# Zavrsni.net
KiCad netlist of a schematic drawn in Altium Designer
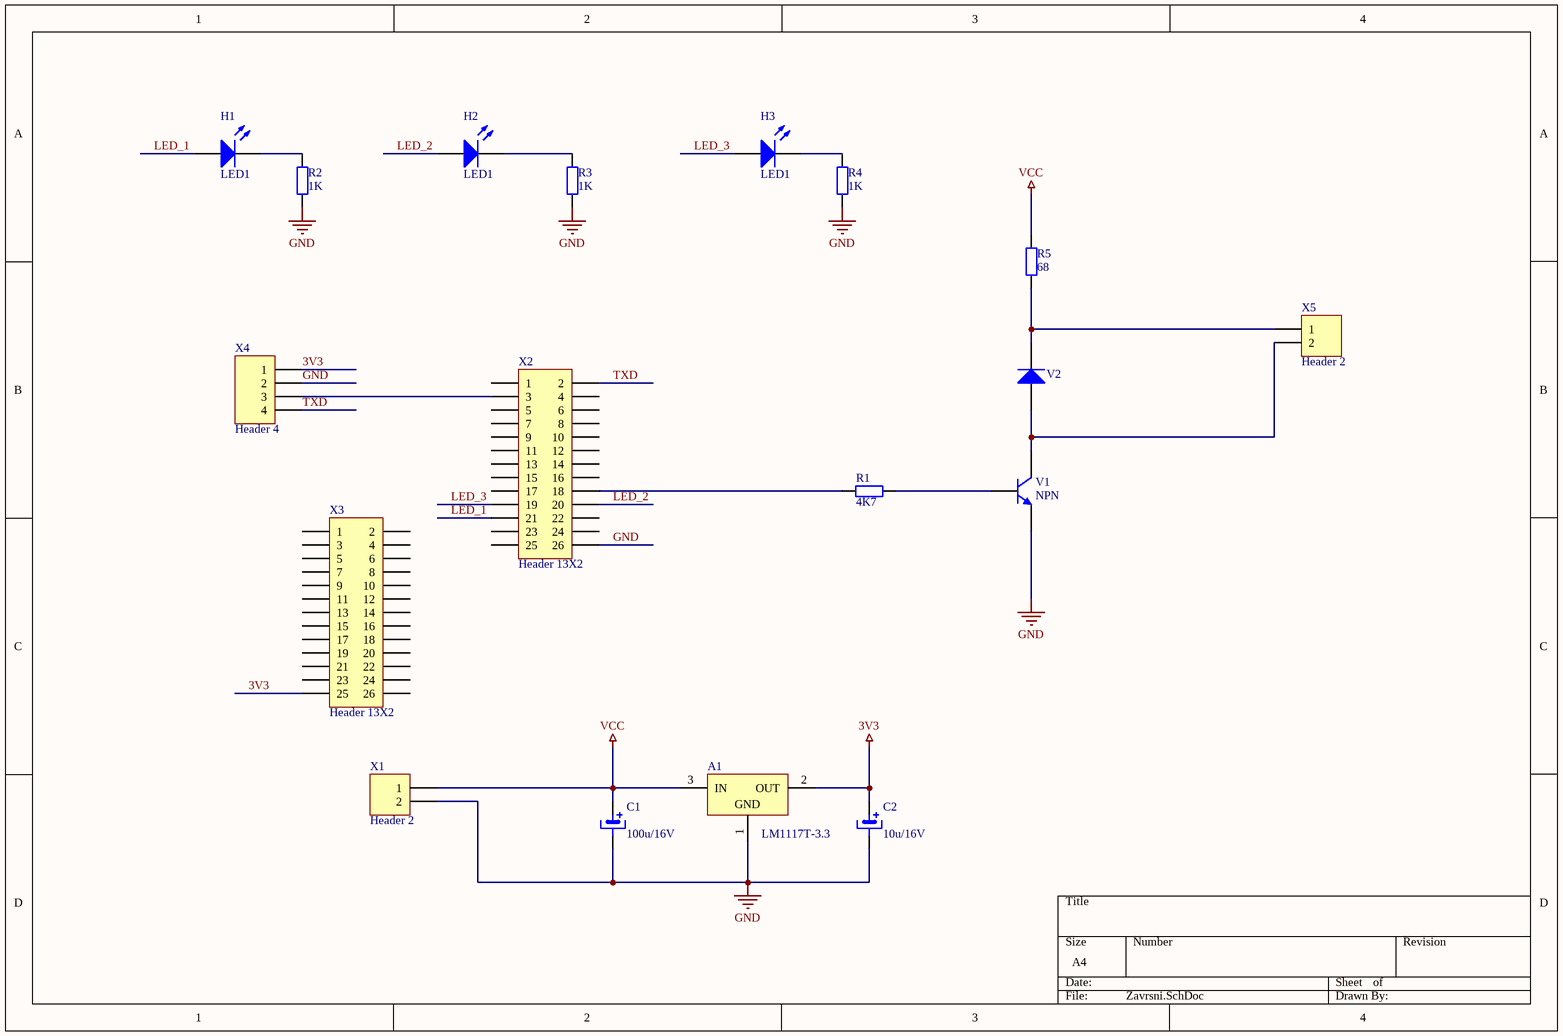
[diagram p0: Zavrsni.SchDoc]

(export (version "E")
  (design (tool "Eeschema 10.0.6"))
  (components
    (comp (ref "A1")
      (value "LM1117T-3.3")
      (footprint "T03B")
      (description "800mA Low-Dropout Linear Regulator, 3-pin TO-220")
      (fields
        (field (name "MANUFACTURER") "National Semiconductor")
        (field (name "PUBLISHER") "Altium Limited")
      )
      (libsource (lib "NSC LDO") (part "LM1117T-3.3"))
    )
    (comp (ref "C1")
      (value "100u/16V")
      (footprint "CAPPR2-5x6.8")
      (description "Electrolytic capacitor")
      (libsource (lib "Zavrsni") (part "Elko"))
    )
    (comp (ref "C2")
      (value "10u/16V")
      (footprint "CAPPR2-5x6.8")
      (description "Electrolytic capacitor")
      (libsource (lib "Zavrsni") (part "Elko"))
    )
    (comp (ref "H1")
      (value "LED1")
      (footprint "LED dioda")
      (description "LED zelena")
      (fields (field (name "PUBLISHER") "Altium Limited"))
      (libsource (lib "Miscellaneous Devices") (part "LED1"))
    )
    (comp (ref "H2")
      (value "LED1")
      (footprint "LED dioda")
      (description "LED žuta")
      (fields (field (name "PUBLISHER") "Altium Limited"))
      (libsource (lib "Miscellaneous Devices") (part "LED1"))
    )
    (comp (ref "H3")
      (value "LED1")
      (footprint "LED dioda")
      (description "LED crvena")
      (fields (field (name "PUBLISHER") "Altium Limited"))
      (libsource (lib "Miscellaneous Devices") (part "LED1"))
    )
    (comp (ref "R1")
      (value "4K7")
      (footprint "AXIAL-0.4")
      (description "Resistor")
      (fields (field (name "PUBLISHER") "Altium Limited"))
      (libsource (lib "") (part "Res2_1"))
    )
    (comp (ref "R2")
      (value "1K")
      (footprint "AXIAL-0.4")
      (description "Resistor")
      (fields (field (name "PUBLISHER") "Altium Limited"))
      (libsource (lib "Miscellaneous Devices") (part "Res2"))
    )
    (comp (ref "R3")
      (value "1K")
      (footprint "AXIAL-0.4")
      (description "Resistor")
      (fields (field (name "PUBLISHER") "Altium Limited"))
      (libsource (lib "Miscellaneous Devices") (part "Res2"))
    )
    (comp (ref "R4")
      (value "1K")
      (footprint "AXIAL-0.4")
      (description "Resistor")
      (fields (field (name "PUBLISHER") "Altium Limited"))
      (libsource (lib "Miscellaneous Devices") (part "Res2"))
    )
    (comp (ref "R5")
      (value "68")
      (footprint "AXIAL-0.4")
      (description "Resistor")
      (fields (field (name "PUBLISHER") "Altium Limited"))
      (libsource (lib "Miscellaneous Devices") (part "Res2"))
    )
    (comp (ref "V1")
      (value "NPN")
      (footprint "TO-226-AA")
      (description "NPN Bipolar Transistor")
      (fields (field (name "PUBLISHER") "Altium Limited"))
      (libsource (lib "Miscellaneous Devices") (part "NPN"))
    )
    (comp (ref "V2")
      (value "Diode 1N4004")
      (footprint "DO-41")
      (description "1 Amp General Purpose Rectifier")
      (fields (field (name "PUBLISHER") "Altium Limited"))
      (libsource (lib "Miscellaneous Devices") (part "Diode 1N4004"))
    )
    (comp (ref "X1")
      (value "Header 2")
      (footprint "HDR1X2")
      (description "Header, 2-Pin")
      (fields (field (name "PUBLISHER") "Altium Limited"))
      (libsource (lib "") (part "Header 2_1"))
    )
    (comp (ref "X2")
      (value "Header 13X2")
      (footprint "HDR2X13")
      (description "Header, 13-Pin, Dual row")
      (fields (field (name "PUBLISHER") "Altium Limited"))
      (libsource (lib "Miscellaneous Connectors") (part "Header 13X2"))
    )
    (comp (ref "X3")
      (value "Header 13X2")
      (footprint "HDR2X13")
      (description "Header, 13-Pin, Dual row")
      (fields (field (name "PUBLISHER") "Altium Limited"))
      (libsource (lib "Miscellaneous Connectors") (part "Header 13X2"))
    )
    (comp (ref "X4")
      (value "Header 4")
      (footprint "HDR1X4")
      (description "Header, 4-Pin")
      (fields (field (name "PUBLISHER") "Altium Limited"))
      (libsource (lib "Miscellaneous Connectors") (part "Header 4"))
    )
    (comp (ref "X5")
      (value "Header 2")
      (footprint "HDR1X2")
      (description "Header, 2-Pin")
      (fields (field (name "PUBLISHER") "Altium Limited"))
      (libsource (lib "Miscellaneous Connectors") (part "Header 2"))
    )
  )
  (nets
    (net (code "1") (name "/LED_1") (class "Default")
      (node (ref "H1") (pin "1") (pinfunction "A_1") (pintype "passive"))
      (node (ref "X2") (pin "21") (pinfunction "21_21") (pintype "passive"))
    )
    (net (code "2") (name "/LED_2") (class "Default")
      (node (ref "H2") (pin "1") (pinfunction "A_1") (pintype "passive"))
      (node (ref "X2") (pin "20") (pinfunction "20_20") (pintype "passive"))
    )
    (net (code "3") (name "/LED_3") (class "Default")
      (node (ref "H3") (pin "1") (pinfunction "A_1") (pintype "passive"))
      (node (ref "X2") (pin "19") (pinfunction "19_19") (pintype "passive"))
    )
    (net (code "4") (name "/TXD") (class "Default")
      (node (ref "X2") (pin "2") (pinfunction "2_2") (pintype "passive"))
      (node (ref "X4") (pin "4") (pinfunction "4_4") (pintype "passive"))
    )
    (net (code "5") (name "3V3") (class "Default")
      (node (ref "A1") (pin "2") (pinfunction "OUT_2") (pintype "power_in"))
      (node (ref "C2") (pin "1") (pinfunction "1_1") (pintype "passive"))
      (node (ref "X3") (pin "25") (pinfunction "25_25") (pintype "passive"))
      (node (ref "X4") (pin "1") (pinfunction "1_1") (pintype "passive"))
    )
    (net (code "6") (name "GND") (class "Default")
      (node (ref "A1") (pin "1") (pinfunction "GND_1") (pintype "power_in"))
      (node (ref "C1") (pin "2") (pinfunction "2_2") (pintype "passive"))
      (node (ref "C2") (pin "2") (pinfunction "2_2") (pintype "passive"))
      (node (ref "R2") (pin "1") (pinfunction "1_1") (pintype "passive"))
      (node (ref "R3") (pin "1") (pinfunction "1_1") (pintype "passive"))
      (node (ref "R4") (pin "1") (pinfunction "1_1") (pintype "passive"))
      (node (ref "V1") (pin "3") (pinfunction "E_3") (pintype "passive"))
      (node (ref "X1") (pin "2") (pinfunction "2_2") (pintype "passive"))
      (node (ref "X2") (pin "26") (pinfunction "26_26") (pintype "passive"))
      (node (ref "X4") (pin "2") (pinfunction "2_2") (pintype "passive"))
    )
    (net (code "7") (name "Net-(H1-K)") (class "Default")
      (node (ref "H1") (pin "2") (pinfunction "K_2") (pintype "passive"))
      (node (ref "R2") (pin "2") (pinfunction "2_2") (pintype "passive"))
    )
    (net (code "8") (name "Net-(H2-K)") (class "Default")
      (node (ref "H2") (pin "2") (pinfunction "K_2") (pintype "passive"))
      (node (ref "R3") (pin "2") (pinfunction "2_2") (pintype "passive"))
    )
    (net (code "9") (name "Net-(H3-K)") (class "Default")
      (node (ref "H3") (pin "2") (pinfunction "K_2") (pintype "passive"))
      (node (ref "R4") (pin "2") (pinfunction "2_2") (pintype "passive"))
    )
    (net (code "10") (name "Net-(R1-Pad1)") (class "Default")
      (node (ref "R1") (pin "1") (pinfunction "1_1") (pintype "passive"))
      (node (ref "X2") (pin "18") (pinfunction "18_18") (pintype "passive"))
    )
    (net (code "11") (name "Net-(V1-B)") (class "Default")
      (node (ref "R1") (pin "2") (pinfunction "2_2") (pintype "passive"))
      (node (ref "V1") (pin "2") (pinfunction "B_2") (pintype "passive"))
    )
    (net (code "12") (name "Net-(V1-C)") (class "Default")
      (node (ref "V1") (pin "1") (pinfunction "C_1") (pintype "passive"))
      (node (ref "V2") (pin "1") (pinfunction "A_1") (pintype "passive"))
      (node (ref "X5") (pin "2") (pinfunction "2_2") (pintype "passive"))
    )
    (net (code "13") (name "Net-(V2-K)") (class "Default")
      (node (ref "R5") (pin "1") (pinfunction "1_1") (pintype "passive"))
      (node (ref "V2") (pin "2") (pinfunction "K_2") (pintype "passive"))
      (node (ref "X5") (pin "1") (pinfunction "1_1") (pintype "passive"))
    )
    (net (code "14") (name "Net-(X2-Pad3)") (class "Default")
      (node (ref "X2") (pin "3") (pinfunction "3_3") (pintype "passive"))
      (node (ref "X4") (pin "3") (pinfunction "3_3") (pintype "passive"))
    )
    (net (code "15") (name "VCC") (class "Default")
      (node (ref "A1") (pin "3") (pinfunction "IN_3") (pintype "power_in"))
      (node (ref "C1") (pin "1") (pinfunction "1_1") (pintype "passive"))
      (node (ref "R5") (pin "2") (pinfunction "2_2") (pintype "passive"))
      (node (ref "X1") (pin "1") (pinfunction "1_1") (pintype "passive"))
    )
    (net (code "16") (name "unconnected-(X2-Pad1)") (class "Default")
      (node (ref "X2") (pin "1") (pinfunction "1_1") (pintype "passive"))
    )
    (net (code "17") (name "unconnected-(X2-Pad4)") (class "Default")
      (node (ref "X2") (pin "4") (pinfunction "4_4") (pintype "passive"))
    )
    (net (code "18") (name "unconnected-(X2-Pad5)") (class "Default")
      (node (ref "X2") (pin "5") (pinfunction "5_5") (pintype "passive"))
    )
    (net (code "19") (name "unconnected-(X2-Pad6)") (class "Default")
      (node (ref "X2") (pin "6") (pinfunction "6_6") (pintype "passive"))
    )
    (net (code "20") (name "unconnected-(X2-Pad7)") (class "Default")
      (node (ref "X2") (pin "7") (pinfunction "7_7") (pintype "passive"))
    )
    (net (code "21") (name "unconnected-(X2-Pad8)") (class "Default")
      (node (ref "X2") (pin "8") (pinfunction "8_8") (pintype "passive"))
    )
    (net (code "22") (name "unconnected-(X2-Pad9)") (class "Default")
      (node (ref "X2") (pin "9") (pinfunction "9_9") (pintype "passive"))
    )
    (net (code "23") (name "unconnected-(X2-Pad10)") (class "Default")
      (node (ref "X2") (pin "10") (pinfunction "10_10") (pintype "passive"))
    )
    (net (code "24") (name "unconnected-(X2-Pad11)") (class "Default")
      (node (ref "X2") (pin "11") (pinfunction "11_11") (pintype "passive"))
    )
    (net (code "25") (name "unconnected-(X2-Pad12)") (class "Default")
      (node (ref "X2") (pin "12") (pinfunction "12_12") (pintype "passive"))
    )
    (net (code "26") (name "unconnected-(X2-Pad13)") (class "Default")
      (node (ref "X2") (pin "13") (pinfunction "13_13") (pintype "passive"))
    )
    (net (code "27") (name "unconnected-(X2-Pad14)") (class "Default")
      (node (ref "X2") (pin "14") (pinfunction "14_14") (pintype "passive"))
    )
    (net (code "28") (name "unconnected-(X2-Pad15)") (class "Default")
      (node (ref "X2") (pin "15") (pinfunction "15_15") (pintype "passive"))
    )
    (net (code "29") (name "unconnected-(X2-Pad16)") (class "Default")
      (node (ref "X2") (pin "16") (pinfunction "16_16") (pintype "passive"))
    )
    (net (code "30") (name "unconnected-(X2-Pad17)") (class "Default")
      (node (ref "X2") (pin "17") (pinfunction "17_17") (pintype "passive"))
    )
    (net (code "31") (name "unconnected-(X2-Pad22)") (class "Default")
      (node (ref "X2") (pin "22") (pinfunction "22_22") (pintype "passive"))
    )
    (net (code "32") (name "unconnected-(X2-Pad23)") (class "Default")
      (node (ref "X2") (pin "23") (pinfunction "23_23") (pintype "passive"))
    )
    (net (code "33") (name "unconnected-(X2-Pad24)") (class "Default")
      (node (ref "X2") (pin "24") (pinfunction "24_24") (pintype "passive"))
    )
    (net (code "34") (name "unconnected-(X2-Pad25)") (class "Default")
      (node (ref "X2") (pin "25") (pinfunction "25_25") (pintype "passive"))
    )
    (net (code "35") (name "unconnected-(X3-Pad1)") (class "Default")
      (node (ref "X3") (pin "1") (pinfunction "1_1") (pintype "passive"))
    )
    (net (code "36") (name "unconnected-(X3-Pad2)") (class "Default")
      (node (ref "X3") (pin "2") (pinfunction "2_2") (pintype "passive"))
    )
    (net (code "37") (name "unconnected-(X3-Pad3)") (class "Default")
      (node (ref "X3") (pin "3") (pinfunction "3_3") (pintype "passive"))
    )
    (net (code "38") (name "unconnected-(X3-Pad4)") (class "Default")
      (node (ref "X3") (pin "4") (pinfunction "4_4") (pintype "passive"))
    )
    (net (code "39") (name "unconnected-(X3-Pad5)") (class "Default")
      (node (ref "X3") (pin "5") (pinfunction "5_5") (pintype "passive"))
    )
    (net (code "40") (name "unconnected-(X3-Pad6)") (class "Default")
      (node (ref "X3") (pin "6") (pinfunction "6_6") (pintype "passive"))
    )
    (net (code "41") (name "unconnected-(X3-Pad7)") (class "Default")
      (node (ref "X3") (pin "7") (pinfunction "7_7") (pintype "passive"))
    )
    (net (code "42") (name "unconnected-(X3-Pad8)") (class "Default")
      (node (ref "X3") (pin "8") (pinfunction "8_8") (pintype "passive"))
    )
    (net (code "43") (name "unconnected-(X3-Pad9)") (class "Default")
      (node (ref "X3") (pin "9") (pinfunction "9_9") (pintype "passive"))
    )
    (net (code "44") (name "unconnected-(X3-Pad10)") (class "Default")
      (node (ref "X3") (pin "10") (pinfunction "10_10") (pintype "passive"))
    )
    (net (code "45") (name "unconnected-(X3-Pad11)") (class "Default")
      (node (ref "X3") (pin "11") (pinfunction "11_11") (pintype "passive"))
    )
    (net (code "46") (name "unconnected-(X3-Pad12)") (class "Default")
      (node (ref "X3") (pin "12") (pinfunction "12_12") (pintype "passive"))
    )
    (net (code "47") (name "unconnected-(X3-Pad13)") (class "Default")
      (node (ref "X3") (pin "13") (pinfunction "13_13") (pintype "passive"))
    )
    (net (code "48") (name "unconnected-(X3-Pad14)") (class "Default")
      (node (ref "X3") (pin "14") (pinfunction "14_14") (pintype "passive"))
    )
    (net (code "49") (name "unconnected-(X3-Pad15)") (class "Default")
      (node (ref "X3") (pin "15") (pinfunction "15_15") (pintype "passive"))
    )
    (net (code "50") (name "unconnected-(X3-Pad16)") (class "Default")
      (node (ref "X3") (pin "16") (pinfunction "16_16") (pintype "passive"))
    )
    (net (code "51") (name "unconnected-(X3-Pad17)") (class "Default")
      (node (ref "X3") (pin "17") (pinfunction "17_17") (pintype "passive"))
    )
    (net (code "52") (name "unconnected-(X3-Pad18)") (class "Default")
      (node (ref "X3") (pin "18") (pinfunction "18_18") (pintype "passive"))
    )
    (net (code "53") (name "unconnected-(X3-Pad19)") (class "Default")
      (node (ref "X3") (pin "19") (pinfunction "19_19") (pintype "passive"))
    )
    (net (code "54") (name "unconnected-(X3-Pad20)") (class "Default")
      (node (ref "X3") (pin "20") (pinfunction "20_20") (pintype "passive"))
    )
    (net (code "55") (name "unconnected-(X3-Pad21)") (class "Default")
      (node (ref "X3") (pin "21") (pinfunction "21_21") (pintype "passive"))
    )
    (net (code "56") (name "unconnected-(X3-Pad22)") (class "Default")
      (node (ref "X3") (pin "22") (pinfunction "22_22") (pintype "passive"))
    )
    (net (code "57") (name "unconnected-(X3-Pad23)") (class "Default")
      (node (ref "X3") (pin "23") (pinfunction "23_23") (pintype "passive"))
    )
    (net (code "58") (name "unconnected-(X3-Pad24)") (class "Default")
      (node (ref "X3") (pin "24") (pinfunction "24_24") (pintype "passive"))
    )
    (net (code "59") (name "unconnected-(X3-Pad26)") (class "Default")
      (node (ref "X3") (pin "26") (pinfunction "26_26") (pintype "passive"))
    )
  )
)
